# SAR_ModDelta.net
KiCad netlist of a schematic drawn in Altium Designer
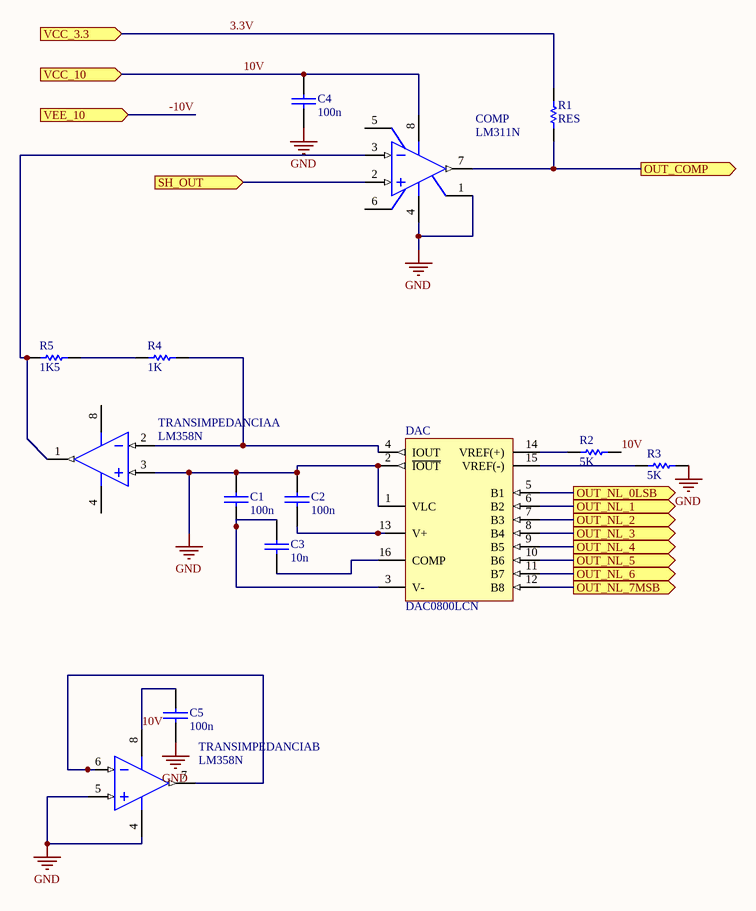
[diagram p0: SAR+ModDelta.SchDoc]

(export (version "E")
  (design (tool "Eeschema 10.0.6"))
  (components
    (comp (ref "C1") (value "100n") (footprint "CAP100") (libsource (lib "LIBEBAL") (part "CAP")))
    (comp (ref "C2") (value "100n") (footprint "CAP100") (libsource (lib "LIBEBAL") (part "CAP")))
    (comp (ref "C3") (value "10n") (footprint "CAP100") (libsource (lib "LIBEBAL") (part "CAP")))
    (comp (ref "C4") (value "100n") (footprint "CAP100") (libsource (lib "LIBEBAL") (part "CAP")))
    (comp (ref "C5") (value "100n") (footprint "CAP100") (libsource (lib "LIBEBAL") (part "CAP")))
    (comp (ref "COMP")
      (value "LM311N")
      (footprint "N08E")
      (description "Voltage Comparator, 8-pin MDIP")
      (fields
        (field (name "MANUFACTURER") "National Semiconductor")
        (field (name "PUBLISHER") "Altium Limited")
      )
      (libsource (lib "NSC Amplifier") (part "LM311N"))
    )
    (comp (ref "DAC")
      (value "DAC0800LCN")
      (footprint "N16E")
      (description "8-Bit D/A Converter, 16-pin MDIP")
      (fields
        (field (name "MANUFACTURER") "National Semiconductor")
        (field (name "PUBLISHER") "Altium Limited")
      )
      (libsource (lib "NSC DAC") (part "DAC0800LCN"))
    )
    (comp (ref "R1") (value "RES") (footprint "RES400") (libsource (lib "LIBEBAL") (part "RES")))
    (comp (ref "R2") (value "5K") (footprint "RES400") (libsource (lib "LIBEBAL") (part "RES")))
    (comp (ref "R3") (value "5K") (footprint "RES400") (libsource (lib "LIBEBAL") (part "RES")))
    (comp (ref "R4") (value "1K") (footprint "RES400") (libsource (lib "LIBEBAL") (part "RES")))
    (comp (ref "R5") (value "1K5") (footprint "RES400") (libsource (lib "LIBEBAL") (part "RES")))
    (comp (ref "TRANSIMPEDANCIA")
      (value "LM358N")
      (footprint "N08E")
      (description "Low Power Dual Operational Amplifier, 8-pin MDIP")
      (fields
        (field (name "MANUFACTURER") "National Semiconductor")
        (field (name "PUBLISHER") "Altium Limited")
      )
      (libsource (lib "NSC Amplifier") (part "LM358N"))
    )
  )
  (nets
    (net (code "2") (name "/3.3V") (class "Default")
      (node (ref "R1") (pin "2") (pinfunction "2_2") (pintype "passive"))
    )
    (net (code "3") (name "/10V") (class "Default")
      (node (ref "C4") (pin "1") (pinfunction "1_1") (pintype "passive"))
      (node (ref "C5") (pin "1") (pinfunction "1_1") (pintype "passive"))
      (node (ref "COMP") (pin "8") (pinfunction "V+_8") (pintype "power_in"))
      (node (ref "R2") (pin "2") (pinfunction "2_2") (pintype "passive"))
      (node (ref "TRANSIMPEDANCIA") (pin "8") (pinfunction "V+_8") (pintype "power_in"))
    )
    (net (code "4") (name "/OUT_COMP") (class "Default")
      (node (ref "COMP") (pin "7") (pinfunction "OUT_7") (pintype "output"))
      (node (ref "R1") (pin "1") (pinfunction "1_1") (pintype "passive"))
    )
    (net (code "5") (name "/OUT_NL_0LSB") (class "Default")
      (node (ref "DAC") (pin "5") (pinfunction "B1_5") (pintype "input"))
    )
    (net (code "6") (name "/OUT_NL_1") (class "Default")
      (node (ref "DAC") (pin "6") (pinfunction "B2_6") (pintype "input"))
    )
    (net (code "7") (name "/OUT_NL_2") (class "Default")
      (node (ref "DAC") (pin "7") (pinfunction "B3_7") (pintype "input"))
    )
    (net (code "8") (name "/OUT_NL_3") (class "Default")
      (node (ref "DAC") (pin "8") (pinfunction "B4_8") (pintype "input"))
    )
    (net (code "9") (name "/OUT_NL_4") (class "Default")
      (node (ref "DAC") (pin "9") (pinfunction "B5_9") (pintype "input"))
    )
    (net (code "10") (name "/OUT_NL_5") (class "Default")
      (node (ref "DAC") (pin "10") (pinfunction "B6_10") (pintype "input"))
    )
    (net (code "11") (name "/OUT_NL_6") (class "Default")
      (node (ref "DAC") (pin "11") (pinfunction "B7_11") (pintype "input"))
    )
    (net (code "12") (name "/OUT_NL_7MSB") (class "Default")
      (node (ref "DAC") (pin "12") (pinfunction "B8_12") (pintype "input"))
    )
    (net (code "13") (name "/SH_OUT") (class "Default")
      (node (ref "COMP") (pin "2") (pinfunction "IN+_2") (pintype "input"))
    )
    (net (code "14") (name "GND") (class "Default")
      (node (ref "C1") (pin "1") (pinfunction "1_1") (pintype "passive"))
      (node (ref "C2") (pin "1") (pinfunction "1_1") (pintype "passive"))
      (node (ref "C4") (pin "2") (pinfunction "2_2") (pintype "passive"))
      (node (ref "C5") (pin "2") (pinfunction "2_2") (pintype "passive"))
      (node (ref "COMP") (pin "1") (pinfunction "GND_1") (pintype "power_in"))
      (node (ref "COMP") (pin "4") (pinfunction "V-_4") (pintype "power_in"))
      (node (ref "DAC") (pin "1") (pinfunction "VLC_1") (pintype "passive"))
      (node (ref "DAC") (pin "2") (pinfunction "~{IOUT}_2") (pintype "output"))
      (node (ref "R3") (pin "2") (pinfunction "2_2") (pintype "passive"))
      (node (ref "TRANSIMPEDANCIA") (pin "3") (pinfunction "INA+_3") (pintype "input"))
      (node (ref "TRANSIMPEDANCIA") (pin "4") (pinfunction "GND_4") (pintype "power_in"))
      (node (ref "TRANSIMPEDANCIA") (pin "5") (pinfunction "INB+_5") (pintype "input"))
    )
    (net (code "15") (name "Net-(COMP-IN-)") (class "Default")
      (node (ref "COMP") (pin "3") (pinfunction "IN-_3") (pintype "input"))
      (node (ref "R5") (pin "1") (pinfunction "1_1") (pintype "passive"))
      (node (ref "TRANSIMPEDANCIA") (pin "1") (pinfunction "OUTA_1") (pintype "output"))
    )
    (net (code "16") (name "Net-(DAC-COMP)") (class "Default")
      (node (ref "C3") (pin "2") (pinfunction "2_2") (pintype "passive"))
      (node (ref "DAC") (pin "16") (pinfunction "COMP_16") (pintype "passive"))
    )
    (net (code "17") (name "Net-(DAC-IOUT)") (class "Default")
      (node (ref "DAC") (pin "4") (pinfunction "IOUT_4") (pintype "output"))
      (node (ref "R4") (pin "2") (pinfunction "2_2") (pintype "passive"))
      (node (ref "TRANSIMPEDANCIA") (pin "2") (pinfunction "INA-_2") (pintype "input"))
    )
    (net (code "18") (name "Net-(DAC-V+)") (class "Default")
      (node (ref "C2") (pin "2") (pinfunction "2_2") (pintype "passive"))
      (node (ref "DAC") (pin "13") (pinfunction "V+_13") (pintype "power_in"))
    )
    (net (code "19") (name "Net-(DAC-V-)") (class "Default")
      (node (ref "C1") (pin "2") (pinfunction "2_2") (pintype "passive"))
      (node (ref "C3") (pin "1") (pinfunction "1_1") (pintype "passive"))
      (node (ref "DAC") (pin "3") (pinfunction "V-_3") (pintype "power_in"))
    )
    (net (code "20") (name "Net-(DAC-VREF(+))") (class "Default")
      (node (ref "DAC") (pin "14") (pinfunction "VREF(+)_14") (pintype "power_in"))
      (node (ref "R2") (pin "1") (pinfunction "1_1") (pintype "passive"))
    )
    (net (code "21") (name "Net-(DAC-VREF(-))") (class "Default")
      (node (ref "DAC") (pin "15") (pinfunction "VREF(-)_15") (pintype "power_in"))
      (node (ref "R3") (pin "1") (pinfunction "1_1") (pintype "passive"))
    )
    (net (code "22") (name "Net-(R4-Pad1)") (class "Default")
      (node (ref "R4") (pin "1") (pinfunction "1_1") (pintype "passive"))
      (node (ref "R5") (pin "2") (pinfunction "2_2") (pintype "passive"))
    )
    (net (code "23") (name "Net-(TRANSIMPEDANCIAB-INB-)") (class "Default")
      (node (ref "TRANSIMPEDANCIA") (pin "6") (pinfunction "INB-_6") (pintype "input"))
      (node (ref "TRANSIMPEDANCIA") (pin "7") (pinfunction "OUTB_7") (pintype "output"))
    )
    (net (code "24") (name "unconnected-(COMP-BAL-Pad5)") (class "Default")
      (node (ref "COMP") (pin "5") (pinfunction "BAL_5") (pintype "passive"))
    )
    (net (code "25") (name "unconnected-(COMP-BAL{slash}STB-Pad6)") (class "Default")
      (node (ref "COMP") (pin "6") (pinfunction "BAL/STB_6") (pintype "passive"))
    )
    (net (code "26") (name "unconnected-(TRANSIMPEDANCIAA-GND-Pad4)") (class "Default")
      (node (ref "TRANSIMPEDANCIA") (pin "4") (pinfunction "GND_4") (pintype "power_in"))
    )
    (net (code "27") (name "unconnected-(TRANSIMPEDANCIAA-V+-Pad8)") (class "Default")
      (node (ref "TRANSIMPEDANCIA") (pin "8") (pinfunction "V+_8") (pintype "power_in"))
    )
  )
)
